# design.net
KiCad netlist of a schematic drawn in Altium Designer
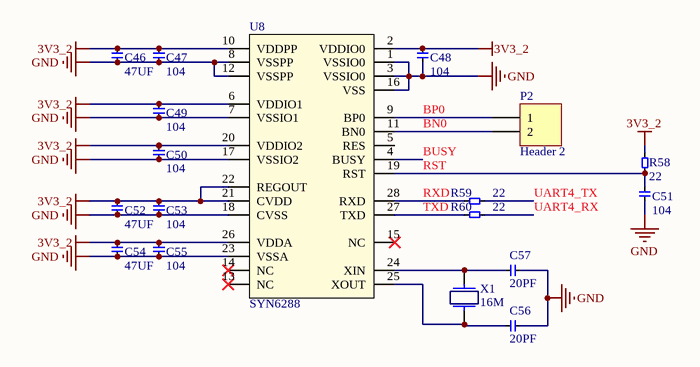
[diagram p0: 语音合成.SchDoc]

(export (version "E")
  (design (tool "Eeschema 10.0.6"))
  (components
    (comp (ref "C46")
      (value "47UF")
      (footprint "C_1206")
      (description "无极性贴片电容")
      (libsource (lib "电阻电容电感库") (part "C_无极贴片"))
    )
    (comp (ref "C47")
      (value "104")
      (footprint "C_0603")
      (description "无极性贴片电容")
      (libsource (lib "电阻电容电感库") (part "C_无极贴片"))
    )
    (comp (ref "C48")
      (value "104")
      (footprint "C_0603")
      (description "无极性贴片电容")
      (libsource (lib "电阻电容电感库") (part "C_无极贴片"))
    )
    (comp (ref "C49")
      (value "104")
      (footprint "C_0603")
      (description "无极性贴片电容")
      (libsource (lib "电阻电容电感库") (part "C_无极贴片"))
    )
    (comp (ref "C50")
      (value "104")
      (footprint "C_0603")
      (description "无极性贴片电容")
      (libsource (lib "电阻电容电感库") (part "C_无极贴片"))
    )
    (comp (ref "C51")
      (value "104")
      (footprint "C_0603")
      (description "无极性贴片电容")
      (libsource (lib "电阻电容电感库") (part "C_无极贴片"))
    )
    (comp (ref "C52")
      (value "47UF")
      (footprint "C_1206")
      (description "无极性贴片电容")
      (libsource (lib "电阻电容电感库") (part "C_无极贴片"))
    )
    (comp (ref "C53")
      (value "104")
      (footprint "C_0603")
      (description "无极性贴片电容")
      (libsource (lib "电阻电容电感库") (part "C_无极贴片"))
    )
    (comp (ref "C54")
      (value "47UF")
      (footprint "C_1206")
      (description "无极性贴片电容")
      (libsource (lib "电阻电容电感库") (part "C_无极贴片"))
    )
    (comp (ref "C55")
      (value "104")
      (footprint "C_0603")
      (description "无极性贴片电容")
      (libsource (lib "电阻电容电感库") (part "C_无极贴片"))
    )
    (comp (ref "C56")
      (value "20PF")
      (footprint "C_0603")
      (description "无极性贴片电容")
      (libsource (lib "电阻电容电感库") (part "C_无极贴片"))
    )
    (comp (ref "C57")
      (value "20PF")
      (footprint "C_0603")
      (description "无极性贴片电容")
      (libsource (lib "电阻电容电感库") (part "C_无极贴片"))
    )
    (comp (ref "P2")
      (value "Header 2")
      (footprint "HDR1X2")
      (description "Header, 2-Pin")
      (fields (field (name "PUBLISHER") "Altium Limited"))
      (libsource (lib "connectors") (part "Header 2"))
    )
    (comp (ref "R58")
      (value "22")
      (footprint "R_0603")
      (description "贴片电阻")
      (libsource (lib "电阻电容电感库") (part "R_贴片"))
    )
    (comp (ref "R59")
      (value "22")
      (footprint "R_0603")
      (description "贴片电阻")
      (libsource (lib "电阻电容电感库") (part "R_贴片"))
    )
    (comp (ref "R60")
      (value "22")
      (footprint "R_0603")
      (description "贴片电阻")
      (libsource (lib "电阻电容电感库") (part "R_贴片"))
    )
    (comp (ref "U8") (value "SYN6288") (footprint "SSOP28") (libsource (lib "王建勇") (part "SYN6288")))
    (comp (ref "X1")
      (value "16M")
      (footprint "XTAL_DIP")
      (fields (field (name "Comment") "xtal"))
      (libsource (lib "lucifer-PCBLIB_V2.0（这是老蒋的）") (part "xtal"))
    )
  )
  (nets
    (net (code "1") (name "/BN0") (class "Default")
      (node (ref "P2") (pin "2") (pinfunction "2_2") (pintype "passive"))
      (node (ref "U8") (pin "11") (pinfunction "BN0_11") (pintype "passive"))
    )
    (net (code "2") (name "/BP0") (class "Default")
      (node (ref "P2") (pin "1") (pinfunction "1_1") (pintype "passive"))
      (node (ref "U8") (pin "9") (pinfunction "BP0_9") (pintype "passive"))
    )
    (net (code "3") (name "/BUSY") (class "Default")
      (node (ref "U8") (pin "4") (pinfunction "BUSY_4") (pintype "passive"))
    )
    (net (code "4") (name "/RST") (class "Default")
      (node (ref "C51") (pin "2") (pinfunction "2_2") (pintype "passive"))
      (node (ref "R58") (pin "1") (pintype "passive"))
      (node (ref "U8") (pin "19") (pinfunction "RST_19") (pintype "passive"))
    )
    (net (code "5") (name "/RXD") (class "Default")
      (node (ref "R59") (pin "1") (pintype "passive"))
      (node (ref "U8") (pin "28") (pinfunction "RXD_28") (pintype "passive"))
    )
    (net (code "6") (name "/TXD") (class "Default")
      (node (ref "R60") (pin "1") (pintype "passive"))
      (node (ref "U8") (pin "27") (pinfunction "TXD_27") (pintype "passive"))
    )
    (net (code "7") (name "/UART4_RX") (class "Default") (node (ref "R60") (pin "2") (pintype "passive")))
    (net (code "8") (name "/UART4_TX") (class "Default") (node (ref "R59") (pin "2") (pintype "passive")))
    (net (code "9") (name "3V3_2") (class "Default")
      (node (ref "C46") (pin "2") (pinfunction "2_2") (pintype "passive"))
      (node (ref "C47") (pin "2") (pinfunction "2_2") (pintype "passive"))
      (node (ref "C48") (pin "2") (pinfunction "2_2") (pintype "passive"))
      (node (ref "C49") (pin "2") (pinfunction "2_2") (pintype "passive"))
      (node (ref "C50") (pin "2") (pinfunction "2_2") (pintype "passive"))
      (node (ref "C52") (pin "2") (pinfunction "2_2") (pintype "passive"))
      (node (ref "C53") (pin "2") (pinfunction "2_2") (pintype "passive"))
      (node (ref "C54") (pin "2") (pinfunction "2_2") (pintype "passive"))
      (node (ref "C55") (pin "2") (pinfunction "2_2") (pintype "passive"))
      (node (ref "R58") (pin "2") (pintype "passive"))
      (node (ref "U8") (pin "10") (pinfunction "VDDPP_10") (pintype "passive"))
      (node (ref "U8") (pin "2") (pinfunction "VDDIO0_2") (pintype "passive"))
      (node (ref "U8") (pin "20") (pinfunction "VDDIO2_20") (pintype "passive"))
      (node (ref "U8") (pin "21") (pinfunction "CVDD_21") (pintype "passive"))
      (node (ref "U8") (pin "22") (pinfunction "REGOUT_22") (pintype "passive"))
      (node (ref "U8") (pin "26") (pinfunction "VDDA_26") (pintype "passive"))
      (node (ref "U8") (pin "6") (pinfunction "VDDIO1_6") (pintype "passive"))
    )
    (net (code "10") (name "GND") (class "Default")
      (node (ref "C46") (pin "1") (pinfunction "1_1") (pintype "passive"))
      (node (ref "C47") (pin "1") (pinfunction "1_1") (pintype "passive"))
      (node (ref "C48") (pin "1") (pinfunction "1_1") (pintype "passive"))
      (node (ref "C49") (pin "1") (pinfunction "1_1") (pintype "passive"))
      (node (ref "C50") (pin "1") (pinfunction "1_1") (pintype "passive"))
      (node (ref "C51") (pin "1") (pinfunction "1_1") (pintype "passive"))
      (node (ref "C52") (pin "1") (pinfunction "1_1") (pintype "passive"))
      (node (ref "C53") (pin "1") (pinfunction "1_1") (pintype "passive"))
      (node (ref "C54") (pin "1") (pinfunction "1_1") (pintype "passive"))
      (node (ref "C55") (pin "1") (pinfunction "1_1") (pintype "passive"))
      (node (ref "C56") (pin "2") (pinfunction "2_2") (pintype "passive"))
      (node (ref "C57") (pin "2") (pinfunction "2_2") (pintype "passive"))
      (node (ref "U8") (pin "1") (pinfunction "VSSIO0_1") (pintype "passive"))
      (node (ref "U8") (pin "12") (pinfunction "VSSPP_12") (pintype "passive"))
      (node (ref "U8") (pin "16") (pinfunction "VSS_16") (pintype "passive"))
      (node (ref "U8") (pin "17") (pinfunction "VSSIO2_17") (pintype "passive"))
      (node (ref "U8") (pin "18") (pinfunction "CVSS_18") (pintype "passive"))
      (node (ref "U8") (pin "23") (pinfunction "VSSA_23") (pintype "passive"))
      (node (ref "U8") (pin "3") (pinfunction "VSSIO0_3") (pintype "passive"))
      (node (ref "U8") (pin "7") (pinfunction "VSSIO1_7") (pintype "passive"))
      (node (ref "U8") (pin "8") (pinfunction "VSSPP_8") (pintype "passive"))
    )
    (net (code "11") (name "Net-(U8-XIN)") (class "Default")
      (node (ref "C57") (pin "1") (pinfunction "1_1") (pintype "passive"))
      (node (ref "U8") (pin "24") (pinfunction "XIN_24") (pintype "passive"))
      (node (ref "X1") (pin "1") (pinfunction "1_1") (pintype "passive"))
    )
    (net (code "12") (name "Net-(U8-XOUT)") (class "Default")
      (node (ref "C56") (pin "1") (pinfunction "1_1") (pintype "passive"))
      (node (ref "U8") (pin "25") (pinfunction "XOUT_25") (pintype "passive"))
      (node (ref "X1") (pin "2") (pinfunction "2_2") (pintype "passive"))
    )
    (net (code "13") (name "unconnected-(U8-NC-Pad13)") (class "Default")
      (node (ref "U8") (pin "13") (pinfunction "NC_13") (pintype "passive+no_connect"))
    )
    (net (code "14") (name "unconnected-(U8-NC-Pad14)") (class "Default")
      (node (ref "U8") (pin "14") (pinfunction "NC_14") (pintype "passive+no_connect"))
    )
    (net (code "15") (name "unconnected-(U8-NC-Pad15)") (class "Default")
      (node (ref "U8") (pin "15") (pinfunction "NC_15") (pintype "passive+no_connect"))
    )
    (net (code "16") (name "unconnected-(U8-RES-Pad5)") (class "Default")
      (node (ref "U8") (pin "5") (pinfunction "RES_5") (pintype "passive"))
    )
  )
)
